# Nixie_IN12.net
KiCad netlist of a schematic drawn in Altium Designer
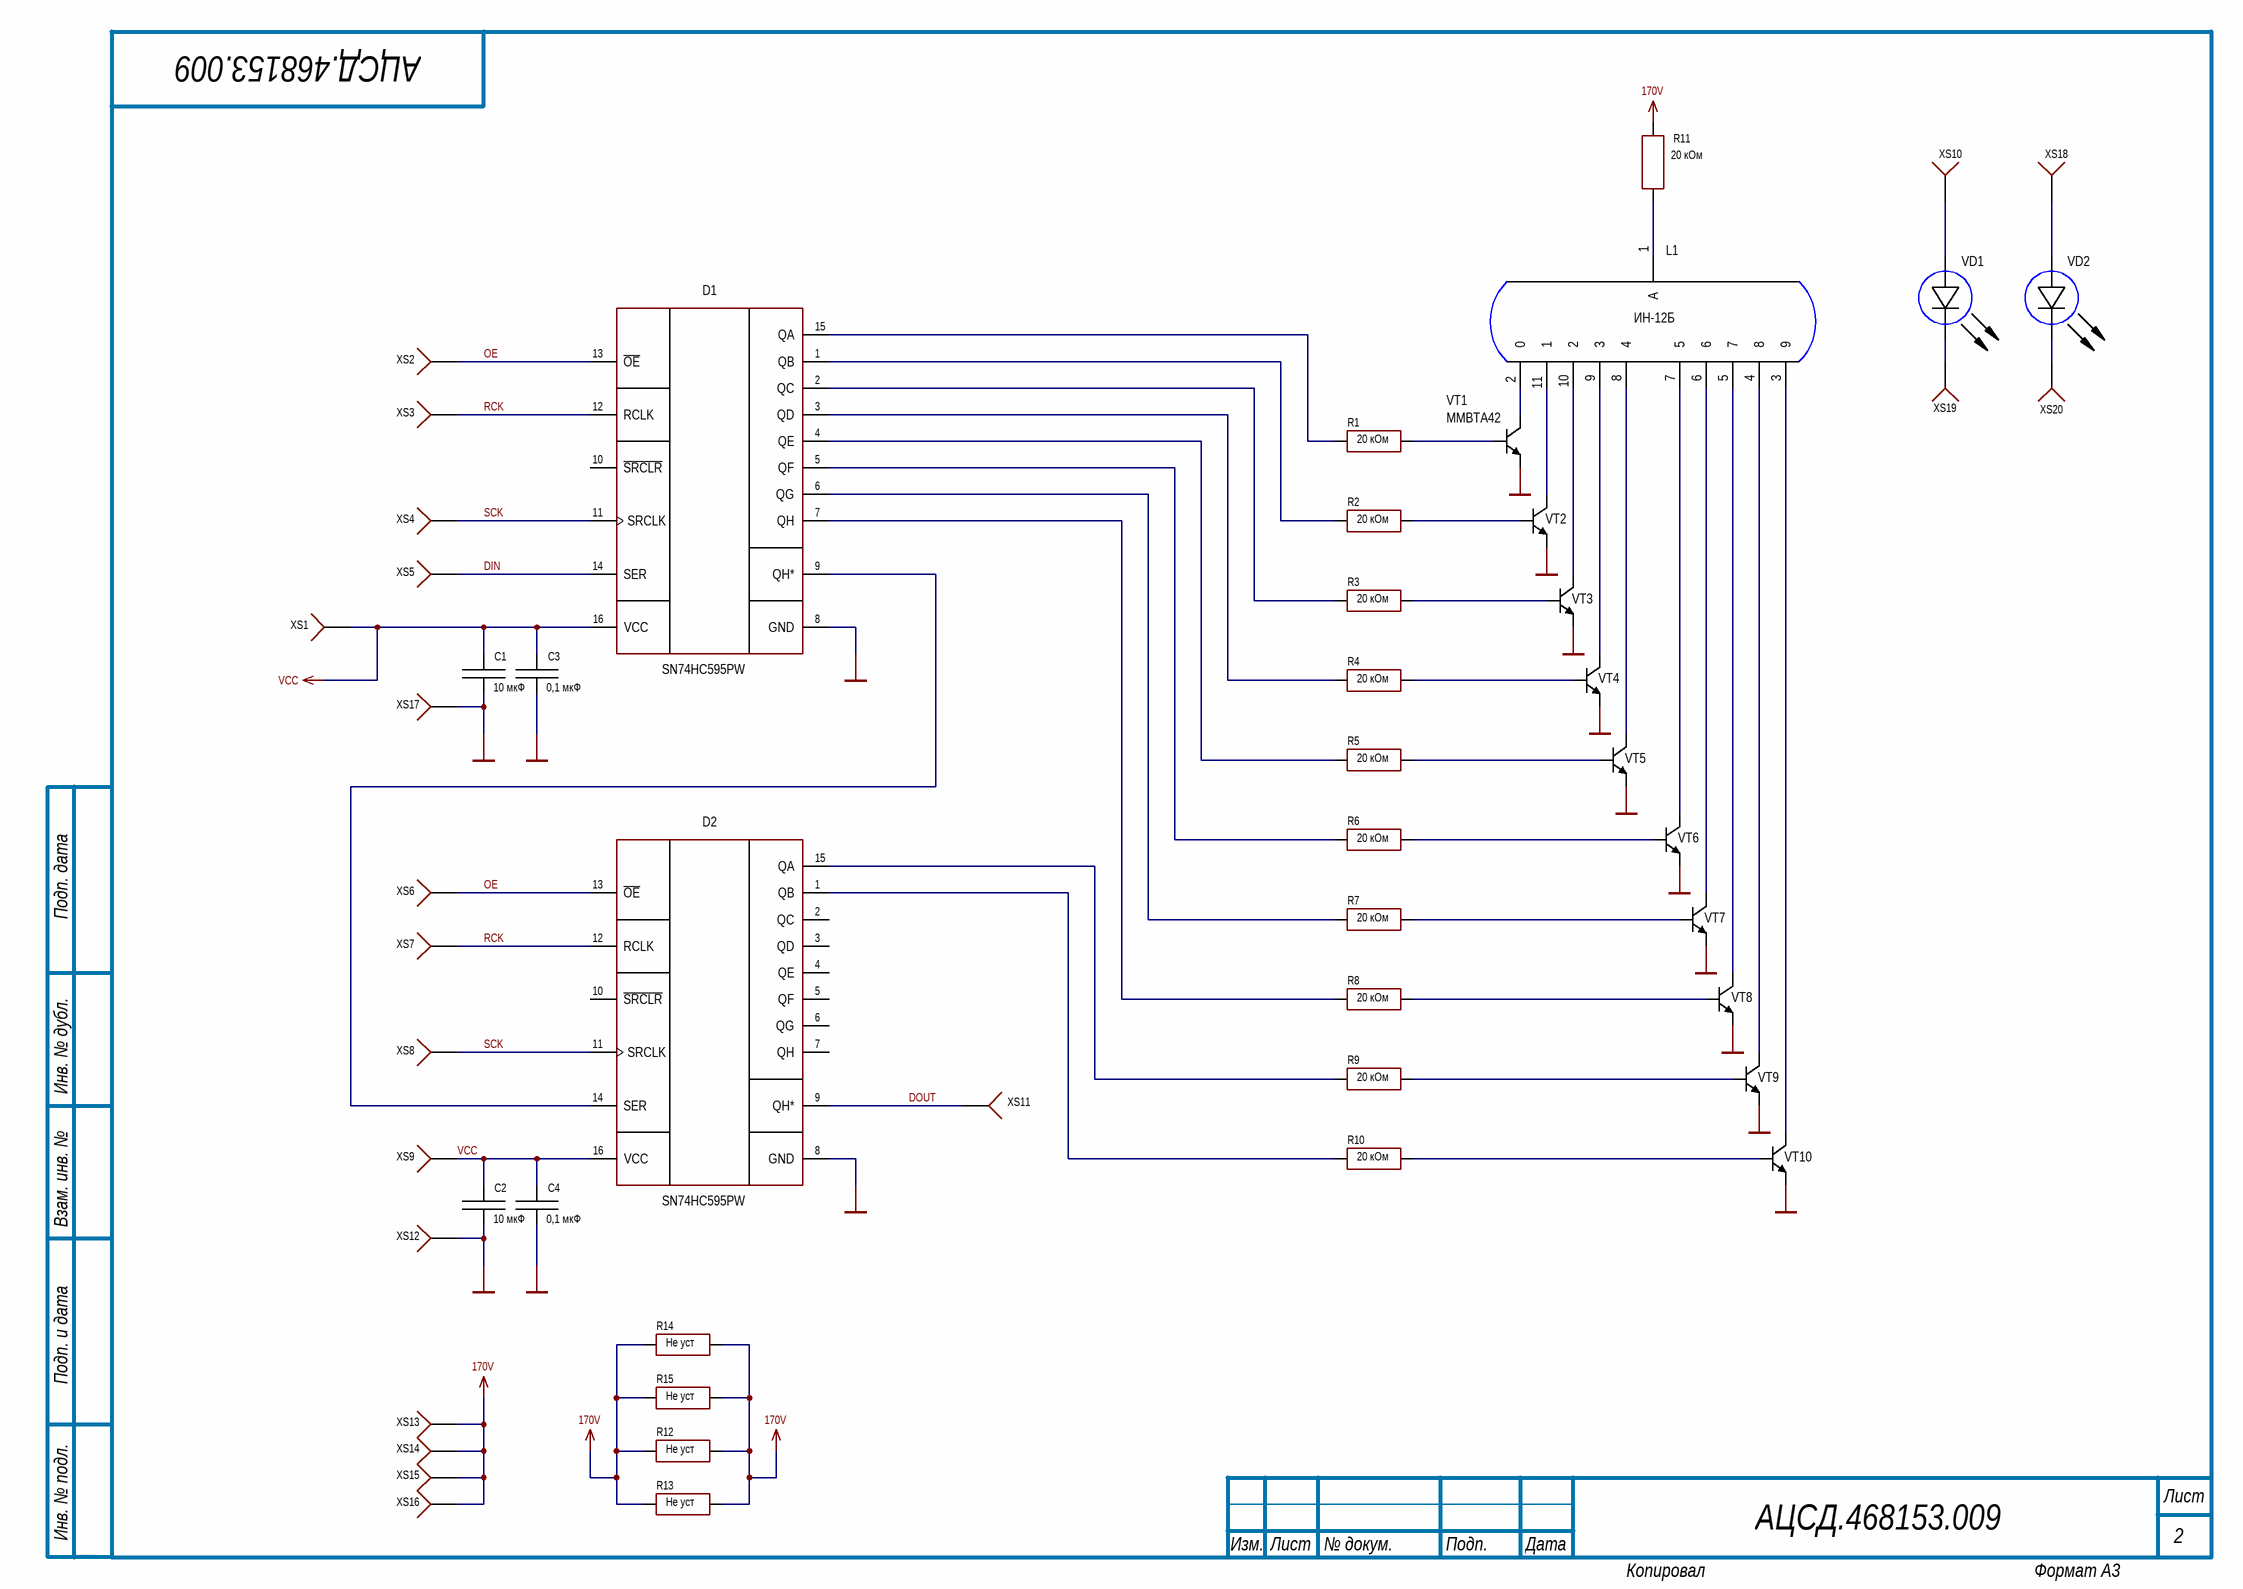
[diagram p0: Nixie_IN12.SchDoc]

(export (version "E")
  (design (tool "Eeschema 10.0.6"))
  (components
    (comp (ref "C1")
      (value "10 мкФ")
      (footprint "CAP: 0603R")
      (fields
        (field (name "MANUFACTURER") "Yageo")
        (field (name "VALUEMANUFACTURERPARTNUMBER") "Ceramic capacitor, 10 мкФ, X7R, ±10%, 16V, 0603, -55...+125°C")
        (field (name "TOLERANCE") "±10%")
      )
      (libsource (lib "Capacitor") (part "Ceramic_0603"))
    )
    (comp (ref "C2")
      (value "10 мкФ")
      (footprint "CAP: 0603R")
      (fields
        (field (name "MANUFACTURER") "Yageo")
        (field (name "VALUEMANUFACTURERPARTNUMBER") "Ceramic capacitor, 10 мкФ, X7R, ±10%, 16V, 0603, -55...+125°C")
        (field (name "TOLERANCE") "±10%")
      )
      (libsource (lib "Capacitor") (part "Ceramic_0603"))
    )
    (comp (ref "C3")
      (value "0,1 мкФ")
      (footprint "CAP: 0603R")
      (fields
        (field (name "MANUFACTURER") "Yageo")
        (field (name "VALUEMANUFACTURERPARTNUMBER") "Ceramic capacitor, 0,1 мкФ, X7R, ±10%, 16V, 0603, -55...+125°C")
        (field (name "TOLERANCE") "±10%")
      )
      (libsource (lib "Capacitor") (part "Ceramic_0603"))
    )
    (comp (ref "C4")
      (value "0,1 мкФ")
      (footprint "CAP: 0603R")
      (fields
        (field (name "MANUFACTURER") "Yageo")
        (field (name "VALUEMANUFACTURERPARTNUMBER") "Ceramic capacitor, 0,1 мкФ, X7R, ±10%, 16V, 0603, -55...+125°C")
        (field (name "TOLERANCE") "±10%")
      )
      (libsource (lib "Capacitor") (part "Ceramic_0603"))
    )
    (comp (ref "D1")
      (value "~")
      (footprint "16-TSSOP(RS)")
      (description "8-Bit Parallel-Out Serial Shift Registers")
      (fields (field (name "MANUFACTURER") "Texas Instruments") (field (name "PARTNUMBER") "SN74HC595PW"))
      (libsource (lib "IC. Interface") (part "SN74HC595DB"))
    )
    (comp (ref "D2")
      (value "~")
      (footprint "16-TSSOP(RS)")
      (description "8-Bit Parallel-Out Serial Shift Registers")
      (fields (field (name "MANUFACTURER") "Texas Instruments") (field (name "PARTNUMBER") "SN74HC595PW"))
      (libsource (lib "IC. Interface") (part "SN74HC595DB"))
    )
    (comp (ref "L1")
      (value "ИН-12")
      (footprint "LAMP: IN-12")
      (fields (field (name "PARTNUMBER") "ИН-12Б"))
      (libsource (lib "Diode") (part "ИН-12"))
    )
    (comp (ref "R1")
      (value "20 кОм")
      (footprint "RES: 0603_ASK")
      (fields
        (field (name "MANUFACTURER") "Yageo")
        (field (name "PARTNUMBER") "RC0603JR-07100RL")
        (field (name "VALUEMANUFACTURERPARTNUMBER") "Resistor film, 20 кОм, ±5%, 0603, 0.1W, -55...+125°C")
      )
      (libsource (lib "Resistor") (part "Resistor_0603"))
    )
    (comp (ref "R2")
      (value "20 кОм")
      (footprint "RES: 0603_ASK")
      (fields
        (field (name "MANUFACTURER") "Yageo")
        (field (name "PARTNUMBER") "RC0603JR-07100RL")
        (field (name "VALUEMANUFACTURERPARTNUMBER") "Resistor film, 20 кОм, ±5%, 0603, 0.1W, -55...+125°C")
      )
      (libsource (lib "Resistor") (part "Resistor_0603"))
    )
    (comp (ref "R3")
      (value "20 кОм")
      (footprint "RES: 0603_ASK")
      (fields
        (field (name "MANUFACTURER") "Yageo")
        (field (name "PARTNUMBER") "RC0603JR-07100RL")
        (field (name "VALUEMANUFACTURERPARTNUMBER") "Resistor film, 20 кОм, ±5%, 0603, 0.1W, -55...+125°C")
      )
      (libsource (lib "Resistor") (part "Resistor_0603"))
    )
    (comp (ref "R4")
      (value "20 кОм")
      (footprint "RES: 0603_ASK")
      (fields
        (field (name "MANUFACTURER") "Yageo")
        (field (name "PARTNUMBER") "RC0603JR-07100RL")
        (field (name "VALUEMANUFACTURERPARTNUMBER") "Resistor film, 20 кОм, ±5%, 0603, 0.1W, -55...+125°C")
      )
      (libsource (lib "Resistor") (part "Resistor_0603"))
    )
    (comp (ref "R5")
      (value "20 кОм")
      (footprint "RES: 0603_ASK")
      (fields
        (field (name "MANUFACTURER") "Yageo")
        (field (name "PARTNUMBER") "RC0603JR-07100RL")
        (field (name "VALUEMANUFACTURERPARTNUMBER") "Resistor film, 20 кОм, ±5%, 0603, 0.1W, -55...+125°C")
      )
      (libsource (lib "Resistor") (part "Resistor_0603"))
    )
    (comp (ref "R6")
      (value "20 кОм")
      (footprint "RES: 0603_ASK")
      (fields
        (field (name "MANUFACTURER") "Yageo")
        (field (name "PARTNUMBER") "RC0603JR-07100RL")
        (field (name "VALUEMANUFACTURERPARTNUMBER") "Resistor film, 20 кОм, ±5%, 0603, 0.1W, -55...+125°C")
      )
      (libsource (lib "Resistor") (part "Resistor_0603"))
    )
    (comp (ref "R7")
      (value "20 кОм")
      (footprint "RES: 0603_ASK")
      (fields
        (field (name "MANUFACTURER") "Yageo")
        (field (name "PARTNUMBER") "RC0603JR-07100RL")
        (field (name "VALUEMANUFACTURERPARTNUMBER") "Resistor film, 20 кОм, ±5%, 0603, 0.1W, -55...+125°C")
      )
      (libsource (lib "Resistor") (part "Resistor_0603"))
    )
    (comp (ref "R8")
      (value "20 кОм")
      (footprint "RES: 0603_ASK")
      (fields
        (field (name "MANUFACTURER") "Yageo")
        (field (name "PARTNUMBER") "RC0603JR-07100RL")
        (field (name "VALUEMANUFACTURERPARTNUMBER") "Resistor film, 20 кОм, ±5%, 0603, 0.1W, -55...+125°C")
      )
      (libsource (lib "Resistor") (part "Resistor_0603"))
    )
    (comp (ref "R9")
      (value "20 кОм")
      (footprint "RES: 0603_ASK")
      (fields
        (field (name "MANUFACTURER") "Yageo")
        (field (name "PARTNUMBER") "RC0603JR-07100RL")
        (field (name "VALUEMANUFACTURERPARTNUMBER") "Resistor film, 20 кОм, ±5%, 0603, 0.1W, -55...+125°C")
      )
      (libsource (lib "Resistor") (part "Resistor_0603"))
    )
    (comp (ref "R10")
      (value "20 кОм")
      (footprint "RES: 0603_ASK")
      (fields
        (field (name "MANUFACTURER") "Yageo")
        (field (name "PARTNUMBER") "RC0603JR-07100RL")
        (field (name "VALUEMANUFACTURERPARTNUMBER") "Resistor film, 20 кОм, ±5%, 0603, 0.1W, -55...+125°C")
      )
      (libsource (lib "Resistor") (part "Resistor_0603"))
    )
    (comp (ref "R11")
      (value "20 кОм")
      (footprint "StandardCase:RES: 2010")
      (fields
        (field (name "MANUFACTURER") "Yageo")
        (field (name "PARTNUMBER") "RC2010JK-07100RL")
        (field (name "VALUEMANUFACTURERPARTNUMBER") "Resistor film, 20 кОм, ±5%, 2010, 0.75W, -55...+125°C")
      )
      (libsource (lib "Resistor") (part "Resistor_2010"))
    )
    (comp (ref "R12")
      (value "Не уст")
      (footprint "RES: 0603_ASK")
      (fields
        (field (name "MANUFACTURER") "Yageo")
        (field (name "PARTNUMBER") "RC0603JR-07100RL")
        (field (name "VALUEMANUFACTURERPARTNUMBER") "Resistor film, Не уст, ±5%, 0603, 0.1W, -55...+125°C")
      )
      (libsource (lib "Resistor") (part "Resistor_0603"))
    )
    (comp (ref "R13")
      (value "Не уст")
      (footprint "RES: 0603_ASK")
      (fields
        (field (name "MANUFACTURER") "Yageo")
        (field (name "PARTNUMBER") "RC0603JR-07100RL")
        (field (name "VALUEMANUFACTURERPARTNUMBER") "Resistor film, Не уст, ±5%, 0603, 0.1W, -55...+125°C")
      )
      (libsource (lib "Resistor") (part "Resistor_0603"))
    )
    (comp (ref "R14")
      (value "Не уст")
      (footprint "RES: 0603_ASK")
      (fields
        (field (name "MANUFACTURER") "Yageo")
        (field (name "PARTNUMBER") "RC0603JR-07100RL")
        (field (name "VALUEMANUFACTURERPARTNUMBER") "Resistor film, Не уст, ±5%, 0603, 0.1W, -55...+125°C")
      )
      (libsource (lib "Resistor") (part "Resistor_0603"))
    )
    (comp (ref "R15")
      (value "Не уст")
      (footprint "RES: 0603_ASK")
      (fields
        (field (name "MANUFACTURER") "Yageo")
        (field (name "PARTNUMBER") "RC0603JR-07100RL")
        (field (name "VALUEMANUFACTURERPARTNUMBER") "Resistor film, Не уст, ±5%, 0603, 0.1W, -55...+125°C")
      )
      (libsource (lib "Resistor") (part "Resistor_0603"))
    )
    (comp (ref "VD1")
      (value "~")
      (footprint "LED: XTEAWT")
      (fields
        (field (name "MANUFACTURER") "CREE")
        (field (name "VALUEMANUFACTURERPARTNUMBER") "LED, , , XP-G2, -55...+150°C")
        (field (name "PARTNUMBER") "XTEAWT - E0 - 0000 - 00000BGE7")
      )
      (libsource (lib "Diode") (part "LED_Salut"))
    )
    (comp (ref "VD2")
      (value "~")
      (footprint "LED: XTEAWT")
      (fields
        (field (name "MANUFACTURER") "CREE")
        (field (name "VALUEMANUFACTURERPARTNUMBER") "LED, , , XP-G2, -55...+150°C")
        (field (name "PARTNUMBER") "XTEAWT - E0 - 0000 - 00000BGE7")
      )
      (libsource (lib "Diode") (part "LED_Salut"))
    )
    (comp (ref "VT1")
      (value "~")
      (footprint "StandardCase:SOT23")
      (fields
        (field (name "MANUFACTURER") "ON Semiconductor")
        (field (name "VALUEMANUFACTURERPARTNUMBER") "NPN transistor, 45V, 100mA, 100MHz, 300mW, 0.6V, 420, SOT-23, -55...+125°C")
        (field (name "PARTNUMBER") "MMBTA42")
      )
      (libsource (lib "Transistor") (part "BJT_NPN_132"))
    )
    (comp (ref "VT2")
      (value "~")
      (footprint "StandardCase:SOT23")
      (fields
        (field (name "MANUFACTURER") "ON Semiconductor")
        (field (name "VALUEMANUFACTURERPARTNUMBER") "NPN transistor, 45V, 100mA, 100MHz, 300mW, 0.6V, 420, SOT-23, -55...+125°C")
        (field (name "PARTNUMBER") "MMBTA42")
      )
      (libsource (lib "Transistor") (part "BJT_NPN_132"))
    )
    (comp (ref "VT3")
      (value "~")
      (footprint "StandardCase:SOT23")
      (fields
        (field (name "MANUFACTURER") "ON Semiconductor")
        (field (name "VALUEMANUFACTURERPARTNUMBER") "NPN transistor, 45V, 100mA, 100MHz, 300mW, 0.6V, 420, SOT-23, -55...+125°C")
        (field (name "PARTNUMBER") "MMBTA42")
      )
      (libsource (lib "Transistor") (part "BJT_NPN_132"))
    )
    (comp (ref "VT4")
      (value "~")
      (footprint "StandardCase:SOT23")
      (fields
        (field (name "MANUFACTURER") "ON Semiconductor")
        (field (name "VALUEMANUFACTURERPARTNUMBER") "NPN transistor, 45V, 100mA, 100MHz, 300mW, 0.6V, 420, SOT-23, -55...+125°C")
        (field (name "PARTNUMBER") "MMBTA42")
      )
      (libsource (lib "Transistor") (part "BJT_NPN_132"))
    )
    (comp (ref "VT5")
      (value "~")
      (footprint "StandardCase:SOT23")
      (fields
        (field (name "MANUFACTURER") "ON Semiconductor")
        (field (name "VALUEMANUFACTURERPARTNUMBER") "NPN transistor, 45V, 100mA, 100MHz, 300mW, 0.6V, 420, SOT-23, -55...+125°C")
        (field (name "PARTNUMBER") "MMBTA42")
      )
      (libsource (lib "Transistor") (part "BJT_NPN_132"))
    )
    (comp (ref "VT6")
      (value "~")
      (footprint "StandardCase:SOT23")
      (fields
        (field (name "MANUFACTURER") "ON Semiconductor")
        (field (name "VALUEMANUFACTURERPARTNUMBER") "NPN transistor, 45V, 100mA, 100MHz, 300mW, 0.6V, 420, SOT-23, -55...+125°C")
        (field (name "PARTNUMBER") "MMBTA42")
      )
      (libsource (lib "Transistor") (part "BJT_NPN_132"))
    )
    (comp (ref "VT7")
      (value "~")
      (footprint "StandardCase:SOT23")
      (fields
        (field (name "MANUFACTURER") "ON Semiconductor")
        (field (name "VALUEMANUFACTURERPARTNUMBER") "NPN transistor, 45V, 100mA, 100MHz, 300mW, 0.6V, 420, SOT-23, -55...+125°C")
        (field (name "PARTNUMBER") "MMBTA42")
      )
      (libsource (lib "Transistor") (part "BJT_NPN_132"))
    )
    (comp (ref "VT8")
      (value "~")
      (footprint "StandardCase:SOT23")
      (fields
        (field (name "MANUFACTURER") "ON Semiconductor")
        (field (name "VALUEMANUFACTURERPARTNUMBER") "NPN transistor, 45V, 100mA, 100MHz, 300mW, 0.6V, 420, SOT-23, -55...+125°C")
        (field (name "PARTNUMBER") "MMBTA42")
      )
      (libsource (lib "Transistor") (part "BJT_NPN_132"))
    )
    (comp (ref "VT9")
      (value "~")
      (footprint "StandardCase:SOT23")
      (fields
        (field (name "MANUFACTURER") "ON Semiconductor")
        (field (name "VALUEMANUFACTURERPARTNUMBER") "NPN transistor, 45V, 100mA, 100MHz, 300mW, 0.6V, 420, SOT-23, -55...+125°C")
        (field (name "PARTNUMBER") "MMBTA42")
      )
      (libsource (lib "Transistor") (part "BJT_NPN_132"))
    )
    (comp (ref "VT10")
      (value "~")
      (footprint "StandardCase:SOT23")
      (fields
        (field (name "MANUFACTURER") "ON Semiconductor")
        (field (name "VALUEMANUFACTURERPARTNUMBER") "NPN transistor, 45V, 100mA, 100MHz, 300mW, 0.6V, 420, SOT-23, -55...+125°C")
        (field (name "PARTNUMBER") "MMBTA42")
      )
      (libsource (lib "Transistor") (part "BJT_NPN_132"))
    )
    (comp (ref "XS1") (value "~") (footprint "CON: PLD-1") (libsource (lib "Connector") (part "Контр.точка")))
    (comp (ref "XS2") (value "~") (footprint "CON: PLD-1") (libsource (lib "Connector") (part "Контр.точка")))
    (comp (ref "XS3") (value "~") (footprint "CON: PLD-1") (libsource (lib "Connector") (part "Контр.точка")))
    (comp (ref "XS4") (value "~") (footprint "CON: PLD-1") (libsource (lib "Connector") (part "Контр.точка")))
    (comp (ref "XS5") (value "~") (footprint "CON: PLD-1") (libsource (lib "Connector") (part "Контр.точка")))
    (comp (ref "XS6") (value "~") (footprint "CON: PLD-1") (libsource (lib "Connector") (part "Контр.точка")))
    (comp (ref "XS7") (value "~") (footprint "CON: PLD-1") (libsource (lib "Connector") (part "Контр.точка")))
    (comp (ref "XS8") (value "~") (footprint "CON: PLD-1") (libsource (lib "Connector") (part "Контр.точка")))
    (comp (ref "XS9") (value "~") (footprint "CON: PLD-1") (libsource (lib "Connector") (part "Контр.точка")))
    (comp (ref "XS10")
      (value "~")
      (footprint "CON: PLD-1")
      (libsource (lib "Connector") (part "Контр.точка"))
    )
    (comp (ref "XS11")
      (value "~")
      (footprint "CON: PLD-1")
      (libsource (lib "Connector") (part "Контр.точка"))
    )
    (comp (ref "XS12")
      (value "~")
      (footprint "CON: PLD-1")
      (libsource (lib "Connector") (part "Контр.точка"))
    )
    (comp (ref "XS13")
      (value "~")
      (footprint "CON: PLD-1")
      (libsource (lib "Connector") (part "Контр.точка"))
    )
    (comp (ref "XS14")
      (value "~")
      (footprint "CON: PLD-1")
      (libsource (lib "Connector") (part "Контр.точка"))
    )
    (comp (ref "XS15")
      (value "~")
      (footprint "CON: PLD-1")
      (libsource (lib "Connector") (part "Контр.точка"))
    )
    (comp (ref "XS16")
      (value "~")
      (footprint "CON: PLD-1")
      (libsource (lib "Connector") (part "Контр.точка"))
    )
    (comp (ref "XS17")
      (value "~")
      (footprint "CON: PLD-1")
      (libsource (lib "Connector") (part "Контр.точка"))
    )
    (comp (ref "XS18")
      (value "~")
      (footprint "CON: PLD-1")
      (libsource (lib "Connector") (part "Контр.точка"))
    )
    (comp (ref "XS19")
      (value "~")
      (footprint "CON: PLD-1")
      (libsource (lib "Connector") (part "Контр.точка"))
    )
    (comp (ref "XS20")
      (value "~")
      (footprint "CON: PLD-1")
      (libsource (lib "Connector") (part "Контр.точка"))
    )
  )
  (nets
    (net (code "1") (name "/DIN") (class "Default")
      (node (ref "D1") (pin "14") (pinfunction "SER_14") (pintype "passive"))
      (node (ref "XS5") (pin "1") (pinfunction "1_1") (pintype "passive"))
    )
    (net (code "2") (name "/DOUT") (class "Default")
      (node (ref "D2") (pin "9") (pinfunction "QH*_9") (pintype "passive"))
      (node (ref "XS11") (pin "1") (pinfunction "1_1") (pintype "passive"))
    )
    (net (code "3") (name "/OE") (class "Default")
      (node (ref "D1") (pin "13") (pinfunction "~{OE}_13") (pintype "passive"))
      (node (ref "D2") (pin "13") (pinfunction "~{OE}_13") (pintype "passive"))
      (node (ref "XS2") (pin "1") (pinfunction "1_1") (pintype "passive"))
      (node (ref "XS6") (pin "1") (pinfunction "1_1") (pintype "passive"))
    )
    (net (code "4") (name "/RCK") (class "Default")
      (node (ref "D1") (pin "12") (pinfunction "RCLK_12") (pintype "passive"))
      (node (ref "D2") (pin "12") (pinfunction "RCLK_12") (pintype "passive"))
      (node (ref "XS3") (pin "1") (pinfunction "1_1") (pintype "passive"))
      (node (ref "XS7") (pin "1") (pinfunction "1_1") (pintype "passive"))
    )
    (net (code "5") (name "/SCK") (class "Default")
      (node (ref "D1") (pin "11") (pinfunction "SRCLK_11") (pintype "passive"))
      (node (ref "D2") (pin "11") (pinfunction "SRCLK_11") (pintype "passive"))
      (node (ref "XS4") (pin "1") (pinfunction "1_1") (pintype "passive"))
      (node (ref "XS8") (pin "1") (pinfunction "1_1") (pintype "passive"))
    )
    (net (code "6") (name "170V") (class "Default")
      (node (ref "R11") (pin "2") (pinfunction "2_2") (pintype "passive"))
      (node (ref "R12") (pin "1") (pinfunction "1_1") (pintype "passive"))
      (node (ref "R12") (pin "2") (pinfunction "2_2") (pintype "passive"))
      (node (ref "R13") (pin "1") (pinfunction "1_1") (pintype "passive"))
      (node (ref "R13") (pin "2") (pinfunction "2_2") (pintype "passive"))
      (node (ref "R14") (pin "1") (pinfunction "1_1") (pintype "passive"))
      (node (ref "R14") (pin "2") (pinfunction "2_2") (pintype "passive"))
      (node (ref "R15") (pin "1") (pinfunction "1_1") (pintype "passive"))
      (node (ref "R15") (pin "2") (pinfunction "2_2") (pintype "passive"))
      (node (ref "XS13") (pin "1") (pinfunction "1_1") (pintype "passive"))
      (node (ref "XS14") (pin "1") (pinfunction "1_1") (pintype "passive"))
      (node (ref "XS15") (pin "1") (pinfunction "1_1") (pintype "passive"))
      (node (ref "XS16") (pin "1") (pinfunction "1_1") (pintype "passive"))
    )
    (net (code "7") (name "GND") (class "Default")
      (node (ref "C1") (pin "1") (pinfunction "1_1") (pintype "power_in"))
      (node (ref "C2") (pin "1") (pinfunction "1_1") (pintype "power_in"))
      (node (ref "C3") (pin "1") (pinfunction "1_1") (pintype "power_in"))
      (node (ref "C4") (pin "1") (pinfunction "1_1") (pintype "power_in"))
      (node (ref "D1") (pin "8") (pinfunction "GND_8") (pintype "passive"))
      (node (ref "D2") (pin "8") (pinfunction "GND_8") (pintype "passive"))
      (node (ref "VT1") (pin "2") (pinfunction "E_2") (pintype "passive"))
      (node (ref "VT10") (pin "2") (pinfunction "E_2") (pintype "passive"))
      (node (ref "VT2") (pin "2") (pinfunction "E_2") (pintype "passive"))
      (node (ref "VT3") (pin "2") (pinfunction "E_2") (pintype "passive"))
      (node (ref "VT4") (pin "2") (pinfunction "E_2") (pintype "passive"))
      (node (ref "VT5") (pin "2") (pinfunction "E_2") (pintype "passive"))
      (node (ref "VT6") (pin "2") (pinfunction "E_2") (pintype "passive"))
      (node (ref "VT7") (pin "2") (pinfunction "E_2") (pintype "passive"))
      (node (ref "VT8") (pin "2") (pinfunction "E_2") (pintype "passive"))
      (node (ref "VT9") (pin "2") (pinfunction "E_2") (pintype "passive"))
      (node (ref "XS12") (pin "1") (pinfunction "1_1") (pintype "passive"))
      (node (ref "XS17") (pin "1") (pinfunction "1_1") (pintype "passive"))
    )
    (net (code "8") (name "Net-(D1-QA)") (class "Default")
      (node (ref "D1") (pin "15") (pinfunction "QA_15") (pintype "passive"))
      (node (ref "R1") (pin "2") (pinfunction "2_2") (pintype "passive"))
    )
    (net (code "9") (name "Net-(D1-QB)") (class "Default")
      (node (ref "D1") (pin "1") (pinfunction "QB_1") (pintype "passive"))
      (node (ref "R2") (pin "2") (pinfunction "2_2") (pintype "passive"))
    )
    (net (code "10") (name "Net-(D1-QC)") (class "Default")
      (node (ref "D1") (pin "2") (pinfunction "QC_2") (pintype "passive"))
      (node (ref "R3") (pin "2") (pinfunction "2_2") (pintype "passive"))
    )
    (net (code "11") (name "Net-(D1-QD)") (class "Default")
      (node (ref "D1") (pin "3") (pinfunction "QD_3") (pintype "passive"))
      (node (ref "R4") (pin "2") (pinfunction "2_2") (pintype "passive"))
    )
    (net (code "12") (name "Net-(D1-QE)") (class "Default")
      (node (ref "D1") (pin "4") (pinfunction "QE_4") (pintype "passive"))
      (node (ref "R5") (pin "2") (pinfunction "2_2") (pintype "passive"))
    )
    (net (code "13") (name "Net-(D1-QF)") (class "Default")
      (node (ref "D1") (pin "5") (pinfunction "QF_5") (pintype "passive"))
      (node (ref "R6") (pin "2") (pinfunction "2_2") (pintype "passive"))
    )
    (net (code "14") (name "Net-(D1-QG)") (class "Default")
      (node (ref "D1") (pin "6") (pinfunction "QG_6") (pintype "passive"))
      (node (ref "R7") (pin "2") (pinfunction "2_2") (pintype "passive"))
    )
    (net (code "15") (name "Net-(D1-QH)") (class "Default")
      (node (ref "D1") (pin "7") (pinfunction "QH_7") (pintype "passive"))
      (node (ref "R8") (pin "2") (pinfunction "2_2") (pintype "passive"))
    )
    (net (code "16") (name "Net-(D1-QH*)") (class "Default")
      (node (ref "D1") (pin "9") (pinfunction "QH*_9") (pintype "passive"))
      (node (ref "D2") (pin "14") (pinfunction "SER_14") (pintype "passive"))
    )
    (net (code "17") (name "Net-(D2-QA)") (class "Default")
      (node (ref "D2") (pin "15") (pinfunction "QA_15") (pintype "passive"))
      (node (ref "R9") (pin "2") (pinfunction "2_2") (pintype "passive"))
    )
    (net (code "18") (name "Net-(D2-QB)") (class "Default")
      (node (ref "D2") (pin "1") (pinfunction "QB_1") (pintype "passive"))
      (node (ref "R10") (pin "2") (pinfunction "2_2") (pintype "passive"))
    )
    (net (code "19") (name "Net-(L1-0)") (class "Default")
      (node (ref "L1") (pin "2") (pinfunction "0_2") (pintype "passive"))
      (node (ref "VT1") (pin "3") (pinfunction "C_3") (pintype "passive"))
    )
    (net (code "20") (name "Net-(L1-1)") (class "Default")
      (node (ref "L1") (pin "11") (pinfunction "1_11") (pintype "passive"))
      (node (ref "VT2") (pin "3") (pinfunction "C_3") (pintype "passive"))
    )
    (net (code "21") (name "Net-(L1-2)") (class "Default")
      (node (ref "L1") (pin "10") (pinfunction "2_10") (pintype "passive"))
      (node (ref "VT3") (pin "3") (pinfunction "C_3") (pintype "passive"))
    )
    (net (code "22") (name "Net-(L1-3)") (class "Default")
      (node (ref "L1") (pin "9") (pinfunction "3_9") (pintype "passive"))
      (node (ref "VT4") (pin "3") (pinfunction "C_3") (pintype "passive"))
    )
    (net (code "23") (name "Net-(L1-4)") (class "Default")
      (node (ref "L1") (pin "8") (pinfunction "4_8") (pintype "passive"))
      (node (ref "VT5") (pin "3") (pinfunction "C_3") (pintype "passive"))
    )
    (net (code "24") (name "Net-(L1-5)") (class "Default")
      (node (ref "L1") (pin "7") (pinfunction "5_7") (pintype "passive"))
      (node (ref "VT6") (pin "3") (pinfunction "C_3") (pintype "passive"))
    )
    (net (code "25") (name "Net-(L1-7)") (class "Default")
      (node (ref "L1") (pin "5") (pinfunction "7_5") (pintype "passive"))
      (node (ref "VT8") (pin "3") (pinfunction "C_3") (pintype "passive"))
    )
    (net (code "26") (name "Net-(L1-8)") (class "Default")
      (node (ref "L1") (pin "4") (pinfunction "8_4") (pintype "passive"))
      (node (ref "VT9") (pin "3") (pinfunction "C_3") (pintype "passive"))
    )
    (net (code "27") (name "Net-(L1-9)") (class "Default")
      (node (ref "L1") (pin "3") (pinfunction "9_3") (pintype "passive"))
      (node (ref "VT10") (pin "3") (pinfunction "C_3") (pintype "passive"))
    )
    (net (code "28") (name "Net-(L1-A)") (class "Default")
      (node (ref "L1") (pin "1") (pinfunction "A_1") (pintype "passive"))
      (node (ref "R11") (pin "1") (pinfunction "1_1") (pintype "passive"))
    )
    (net (code "29") (name "Net-(VD1-A)") (class "Default")
      (node (ref "VD1") (pin "1") (pinfunction "A_1") (pintype "passive"))
      (node (ref "XS10") (pin "1") (pinfunction "1_1") (pintype "passive"))
    )
    (net (code "30") (name "Net-(VD1-C)") (class "Default")
      (node (ref "VD1") (pin "2") (pinfunction "C_2") (pintype "passive"))
      (node (ref "XS19") (pin "1") (pinfunction "1_1") (pintype "passive"))
    )
    (net (code "31") (name "Net-(VD2-A)") (class "Default")
      (node (ref "VD2") (pin "1") (pinfunction "A_1") (pintype "passive"))
      (node (ref "XS18") (pin "1") (pinfunction "1_1") (pintype "passive"))
    )
    (net (code "32") (name "Net-(VD2-C)") (class "Default")
      (node (ref "VD2") (pin "2") (pinfunction "C_2") (pintype "passive"))
      (node (ref "XS20") (pin "1") (pinfunction "1_1") (pintype "passive"))
    )
    (net (code "33") (name "Net-(VT1-B)") (class "Default")
      (node (ref "R1") (pin "1") (pinfunction "1_1") (pintype "passive"))
      (node (ref "VT1") (pin "1") (pinfunction "B_1") (pintype "passive"))
    )
    (net (code "34") (name "Net-(VT2-B)") (class "Default")
      (node (ref "R2") (pin "1") (pinfunction "1_1") (pintype "passive"))
      (node (ref "VT2") (pin "1") (pinfunction "B_1") (pintype "passive"))
    )
    (net (code "35") (name "Net-(VT3-B)") (class "Default")
      (node (ref "R3") (pin "1") (pinfunction "1_1") (pintype "passive"))
      (node (ref "VT3") (pin "1") (pinfunction "B_1") (pintype "passive"))
    )
    (net (code "36") (name "Net-(VT4-B)") (class "Default")
      (node (ref "R4") (pin "1") (pinfunction "1_1") (pintype "passive"))
      (node (ref "VT4") (pin "1") (pinfunction "B_1") (pintype "passive"))
    )
    (net (code "37") (name "Net-(VT5-B)") (class "Default")
      (node (ref "R5") (pin "1") (pinfunction "1_1") (pintype "passive"))
      (node (ref "VT5") (pin "1") (pinfunction "B_1") (pintype "passive"))
    )
    (net (code "38") (name "Net-(VT6-B)") (class "Default")
      (node (ref "R6") (pin "1") (pinfunction "1_1") (pintype "passive"))
      (node (ref "VT6") (pin "1") (pinfunction "B_1") (pintype "passive"))
    )
    (net (code "39") (name "Net-(VT7-B)") (class "Default")
      (node (ref "R7") (pin "1") (pinfunction "1_1") (pintype "passive"))
      (node (ref "VT7") (pin "1") (pinfunction "B_1") (pintype "passive"))
    )
    (net (code "40") (name "Net-(VT7-C)") (class "Default")
      (node (ref "L1") (pin "6") (pinfunction "6_6") (pintype "passive"))
      (node (ref "VT7") (pin "3") (pinfunction "C_3") (pintype "passive"))
    )
    (net (code "41") (name "Net-(VT8-B)") (class "Default")
      (node (ref "R8") (pin "1") (pinfunction "1_1") (pintype "passive"))
      (node (ref "VT8") (pin "1") (pinfunction "B_1") (pintype "passive"))
    )
    (net (code "42") (name "Net-(VT9-B)") (class "Default")
      (node (ref "R9") (pin "1") (pinfunction "1_1") (pintype "passive"))
      (node (ref "VT9") (pin "1") (pinfunction "B_1") (pintype "passive"))
    )
    (net (code "43") (name "Net-(VT10-B)") (class "Default")
      (node (ref "R10") (pin "1") (pinfunction "1_1") (pintype "passive"))
      (node (ref "VT10") (pin "1") (pinfunction "B_1") (pintype "passive"))
    )
    (net (code "44") (name "VCC") (class "Default")
      (node (ref "C1") (pin "2") (pinfunction "2_2") (pintype "power_in"))
      (node (ref "C2") (pin "2") (pinfunction "2_2") (pintype "power_in"))
      (node (ref "C3") (pin "2") (pinfunction "2_2") (pintype "power_in"))
      (node (ref "C4") (pin "2") (pinfunction "2_2") (pintype "power_in"))
      (node (ref "D1") (pin "16") (pinfunction "VCC_16") (pintype "passive"))
      (node (ref "D2") (pin "16") (pinfunction "VCC_16") (pintype "passive"))
      (node (ref "XS1") (pin "1") (pinfunction "1_1") (pintype "passive"))
      (node (ref "XS9") (pin "1") (pinfunction "1_1") (pintype "passive"))
    )
    (net (code "45") (name "unconnected-(D1-~{SRCLR}-Pad10)") (class "Default")
      (node (ref "D1") (pin "10") (pinfunction "~{SRCLR}_10") (pintype "passive"))
    )
    (net (code "46") (name "unconnected-(D2-QC-Pad2)") (class "Default")
      (node (ref "D2") (pin "2") (pinfunction "QC_2") (pintype "passive"))
    )
    (net (code "47") (name "unconnected-(D2-QD-Pad3)") (class "Default")
      (node (ref "D2") (pin "3") (pinfunction "QD_3") (pintype "passive"))
    )
    (net (code "48") (name "unconnected-(D2-QE-Pad4)") (class "Default")
      (node (ref "D2") (pin "4") (pinfunction "QE_4") (pintype "passive"))
    )
    (net (code "49") (name "unconnected-(D2-QF-Pad5)") (class "Default")
      (node (ref "D2") (pin "5") (pinfunction "QF_5") (pintype "passive"))
    )
    (net (code "50") (name "unconnected-(D2-QG-Pad6)") (class "Default")
      (node (ref "D2") (pin "6") (pinfunction "QG_6") (pintype "passive"))
    )
    (net (code "51") (name "unconnected-(D2-QH-Pad7)") (class "Default")
      (node (ref "D2") (pin "7") (pinfunction "QH_7") (pintype "passive"))
    )
    (net (code "52") (name "unconnected-(D2-~{SRCLR}-Pad10)") (class "Default")
      (node (ref "D2") (pin "10") (pinfunction "~{SRCLR}_10") (pintype "passive"))
    )
  )
)
